# bilancia_smart_pezzi_amp.net
KiCad netlist of a schematic drawn in EAGLE
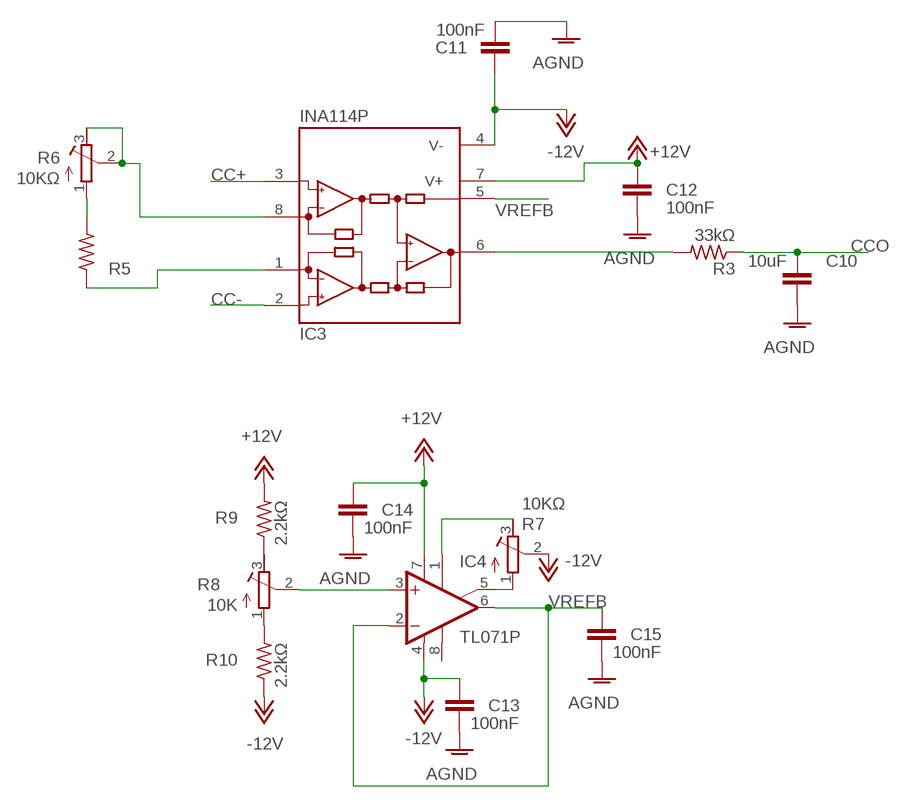
[diagram p0: schematic, sheet 1]

(export (version "E")
  (design (tool "Eeschema 10.0.6"))
  (components
    (comp (ref "C10")
      (value "10uF")
      (footprint "eagle-import:C2.5-2")
      (libsource (lib "eagle-import") (part "C2.5/2"))
    )
    (comp (ref "C11")
      (value "100nF")
      (footprint "eagle-import:C2.5-2")
      (libsource (lib "eagle-import") (part "C2.5/2"))
    )
    (comp (ref "C12")
      (value "100nF")
      (footprint "eagle-import:C2.5-2")
      (libsource (lib "eagle-import") (part "C2.5/2"))
    )
    (comp (ref "C13")
      (value "100nF")
      (footprint "eagle-import:C2.5-2")
      (libsource (lib "eagle-import") (part "C2.5/2"))
    )
    (comp (ref "C14")
      (value "100nF")
      (footprint "eagle-import:C2.5-2")
      (libsource (lib "eagle-import") (part "C2.5/2"))
    )
    (comp (ref "C15")
      (value "100nF")
      (footprint "eagle-import:C2.5-2")
      (libsource (lib "eagle-import") (part "C2.5/2"))
    )
    (comp (ref "IC3")
      (value "INA114P")
      (footprint "eagle-import:DIL08")
      (fields (field (name "MF") "TEXAS INSTRUMENTS") (field (name "MPN") "INA114BP"))
      (libsource (lib "eagle-import") (part "INA114P"))
    )
    (comp (ref "IC4")
      (value "TL071P")
      (footprint "eagle-import:DIL08")
      (libsource (lib "eagle-import") (part "TL071P"))
    )
    (comp (ref "R3")
      (value "33kΩ")
      (footprint "eagle-import:0207_10")
      (libsource (lib "eagle-import") (part "R-US_0207/10"))
    )
    (comp (ref "R5")
      (value "R-US_0207/10")
      (footprint "eagle-import:0207_10")
      (libsource (lib "eagle-import") (part "R-US_0207/10"))
    )
    (comp (ref "R6")
      (value "10KΩ")
      (footprint "eagle-import:RTRIM64W")
      (libsource (lib "eagle-import") (part "R-TRIMM64W"))
    )
    (comp (ref "R7")
      (value "10KΩ")
      (footprint "eagle-import:RTRIM64W")
      (libsource (lib "eagle-import") (part "R-TRIMM64W"))
    )
    (comp (ref "R8")
      (value "10K")
      (footprint "eagle-import:RTRIM64W")
      (libsource (lib "eagle-import") (part "R-TRIMM64W"))
    )
    (comp (ref "R9")
      (value "2.2kΩ")
      (footprint "eagle-import:0207_10")
      (libsource (lib "eagle-import") (part "R-US_0207/10"))
    )
    (comp (ref "R10")
      (value "2.2kΩ")
      (footprint "eagle-import:0207_10")
      (libsource (lib "eagle-import") (part "R-US_0207/10"))
    )
  )
  (nets
    (net (code "1") (name "+12V") (class "Default")
      (node (ref "C12") (pin "2") (pinfunction "2_2") (pintype "passive"))
      (node (ref "C14") (pin "2") (pinfunction "2_2") (pintype "passive"))
      (node (ref "IC3") (pin "7") (pinfunction "V+_7") (pintype "power_in"))
      (node (ref "IC4") (pin "7") (pinfunction "V+_7") (pintype "power_in"))
      (node (ref "R9") (pin "2") (pinfunction "2_2") (pintype "passive"))
    )
    (net (code "2") (name "-12V") (class "Default")
      (node (ref "C11") (pin "2") (pinfunction "2_2") (pintype "passive"))
      (node (ref "C13") (pin "2") (pinfunction "2_2") (pintype "passive"))
      (node (ref "IC3") (pin "4") (pinfunction "V-_4") (pintype "power_in"))
      (node (ref "IC4") (pin "4") (pinfunction "V-_4") (pintype "power_in"))
      (node (ref "R10") (pin "1") (pinfunction "1_1") (pintype "passive"))
      (node (ref "R7") (pin "2") (pinfunction "S_2") (pintype "passive"))
    )
    (net (code "3") (name "/CC+") (class "Default")
      (node (ref "IC3") (pin "3") (pinfunction "+IN_3") (pintype "input"))
    )
    (net (code "4") (name "/CC-") (class "Default")
      (node (ref "IC3") (pin "2") (pinfunction "-IN_2") (pintype "input"))
    )
    (net (code "5") (name "/CCO") (class "Default")
      (node (ref "C10") (pin "2") (pinfunction "2_2") (pintype "passive"))
      (node (ref "R3") (pin "1") (pinfunction "1_1") (pintype "passive"))
    )
    (net (code "6") (name "/VREFB") (class "Default")
      (node (ref "C15") (pin "2") (pinfunction "2_2") (pintype "passive"))
      (node (ref "IC3") (pin "5") (pinfunction "REF_5") (pintype "passive"))
      (node (ref "IC4") (pin "2") (pinfunction "-IN_2") (pintype "input"))
      (node (ref "IC4") (pin "6") (pinfunction "OUT_6") (pintype "output"))
    )
    (net (code "7") (name "AGND") (class "Default")
      (node (ref "C10") (pin "1") (pinfunction "1_1") (pintype "passive"))
      (node (ref "C11") (pin "1") (pinfunction "1_1") (pintype "passive"))
      (node (ref "C12") (pin "1") (pinfunction "1_1") (pintype "passive"))
      (node (ref "C13") (pin "1") (pinfunction "1_1") (pintype "passive"))
      (node (ref "C14") (pin "1") (pinfunction "1_1") (pintype "passive"))
      (node (ref "C15") (pin "1") (pinfunction "1_1") (pintype "passive"))
    )
    (net (code "8") (name "Net-(IC3-OUT)") (class "Default")
      (node (ref "IC3") (pin "6") (pinfunction "OUT_6") (pintype "output"))
      (node (ref "R3") (pin "2") (pinfunction "2_2") (pintype "passive"))
    )
    (net (code "9") (name "Net-(IC3-RG-Pad1)") (class "Default")
      (node (ref "IC3") (pin "1") (pinfunction "RG_1") (pintype "passive"))
      (node (ref "R5") (pin "1") (pinfunction "1_1") (pintype "passive"))
    )
    (net (code "10") (name "Net-(IC4-+IN)") (class "Default")
      (node (ref "IC4") (pin "3") (pinfunction "+IN_3") (pintype "input"))
      (node (ref "R8") (pin "2") (pinfunction "S_2") (pintype "passive"))
    )
    (net (code "11") (name "Net-(IC4-ON1)") (class "Default")
      (node (ref "IC4") (pin "1") (pinfunction "ON1_1") (pintype "passive"))
      (node (ref "R7") (pin "3") (pinfunction "A_3") (pintype "passive"))
    )
    (net (code "12") (name "Net-(IC4-ON2)") (class "Default")
      (node (ref "IC4") (pin "5") (pinfunction "ON2_5") (pintype "passive"))
      (node (ref "R7") (pin "1") (pinfunction "E_1") (pintype "passive"))
    )
    (net (code "13") (name "Net-(R6-A)") (class "Default")
      (node (ref "IC3") (pin "8") (pinfunction "RG_8") (pintype "passive"))
      (node (ref "R6") (pin "2") (pinfunction "S_2") (pintype "passive"))
      (node (ref "R6") (pin "3") (pinfunction "A_3") (pintype "passive"))
    )
    (net (code "14") (name "Net-(R6-E)") (class "Default")
      (node (ref "R5") (pin "2") (pinfunction "2_2") (pintype "passive"))
      (node (ref "R6") (pin "1") (pinfunction "E_1") (pintype "passive"))
    )
    (net (code "15") (name "Net-(R8-A)") (class "Default")
      (node (ref "R8") (pin "3") (pinfunction "A_3") (pintype "passive"))
      (node (ref "R9") (pin "1") (pinfunction "1_1") (pintype "passive"))
    )
    (net (code "16") (name "Net-(R8-E)") (class "Default")
      (node (ref "R10") (pin "2") (pinfunction "2_2") (pintype "passive"))
      (node (ref "R8") (pin "1") (pinfunction "E_1") (pintype "passive"))
    )
    (net (code "17") (name "unconnected-(IC4-OPT-Pad8)") (class "Default")
      (node (ref "IC4") (pin "8") (pinfunction "OPT_8") (pintype "passive"))
    )
  )
)
